# Bluetooth_Bee__Standalone_v1_0.net
KiCad netlist of a schematic drawn in EAGLE
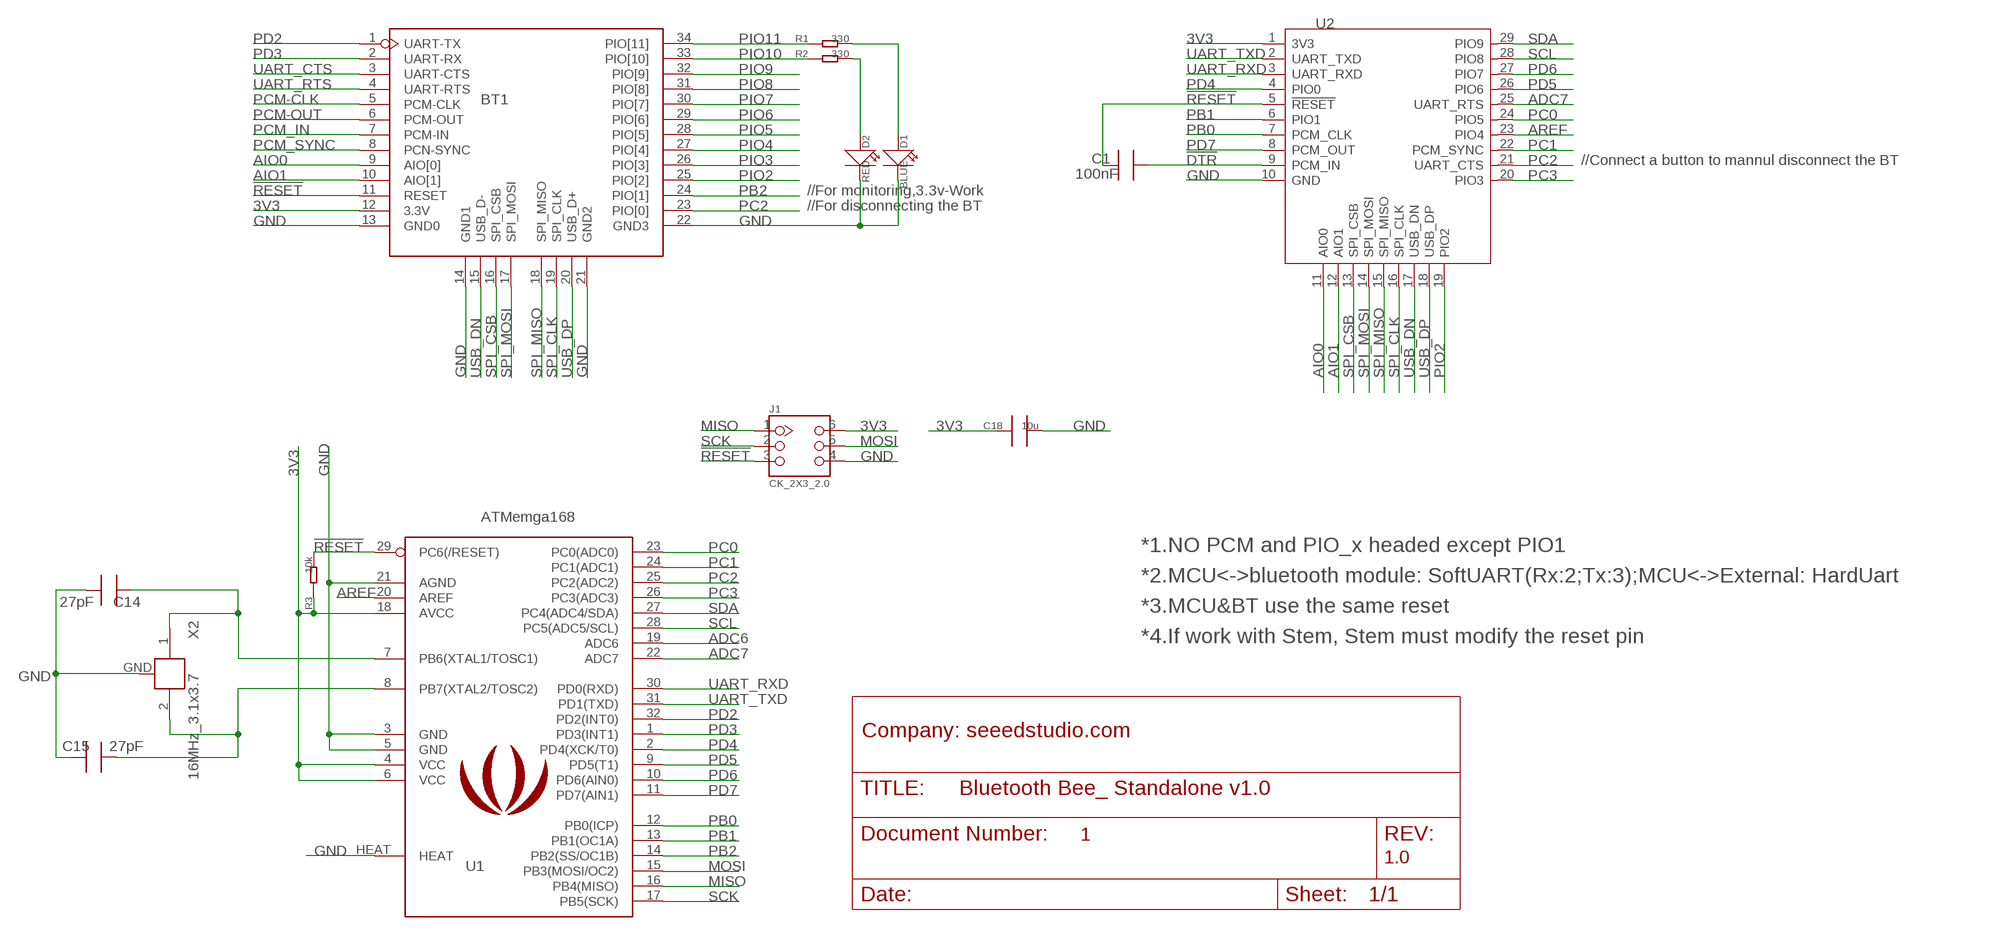
[diagram p0: schematic, sheet 1]

(export (version "E")
  (design (tool "Eeschema 10.0.6"))
  (components
    (comp (ref "BT1")
      (value "SERIAL_BLUETEETHSMT")
      (footprint "eagle-import:SERIAL_BLUETEETH")
      (libsource (lib "eagle-import") (part "SERIAL_BLUETEETHSMT"))
    )
    (comp (ref "C1")
      (value "100nF")
      (footprint "eagle-import:0603_S")
      (libsource (lib "eagle-import") (part "C0603_S"))
    )
    (comp (ref "C14")
      (value "27pF")
      (footprint "eagle-import:0603")
      (libsource (lib "eagle-import") (part "C0603"))
    )
    (comp (ref "C15")
      (value "27pF")
      (footprint "eagle-import:0603")
      (libsource (lib "eagle-import") (part "C0603"))
    )
    (comp (ref "C18")
      (value "10u")
      (footprint "eagle-import:0805")
      (libsource (lib "eagle-import") (part "C0805"))
    )
    (comp (ref "D1")
      (value "BLUE")
      (footprint "eagle-import:LED0603")
      (libsource (lib "eagle-import") (part "LED0603"))
    )
    (comp (ref "D2")
      (value "RED")
      (footprint "eagle-import:LED0603")
      (libsource (lib "eagle-import") (part "LED0603"))
    )
    (comp (ref "J1")
      (value "CK_2X3_2.0")
      (footprint "eagle-import:CK_2X3_2.0")
      (libsource (lib "eagle-import") (part "CK_2X3_2.0"))
    )
    (comp (ref "LOGO1")
      (value "LOGO_SILK")
      (footprint "eagle-import:LOGO_SILK")
      (libsource (lib "eagle-import") (part "LOGO_SILK"))
    )
    (comp (ref "R1")
      (value "330")
      (footprint "eagle-import:0603")
      (libsource (lib "eagle-import") (part "R0603"))
    )
    (comp (ref "R2")
      (value "330")
      (footprint "eagle-import:0603")
      (libsource (lib "eagle-import") (part "R0603"))
    )
    (comp (ref "R3")
      (value "10k")
      (footprint "eagle-import:0603_S@1")
      (libsource (lib "eagle-import") (part "R0603_S"))
    )
    (comp (ref "U1")
      (value "ATMemga168")
      (footprint "eagle-import:MLF32X")
      (libsource (lib "eagle-import") (part "MEGA8"))
    )
    (comp (ref "U2")
      (value "BLUTOOTHBEE-MS")
      (footprint "eagle-import:29P-DIP-2.0")
      (libsource (lib "eagle-import") (part "BLUTOOTHBEE-MS"))
    )
    (comp (ref "X2")
      (value "16MHz_3.1x3.7")
      (footprint "eagle-import:XTAL_NC")
      (libsource (lib "eagle-import") (part "XTAL_NCHOZ"))
    )
  )
  (nets
    (net (code "1") (name "/3V3") (class "Default")
      (node (ref "BT1") (pin "12") (pinfunction "3.3V_12") (pintype "bidirectional"))
      (node (ref "C18") (pin "1") (pinfunction "1_1") (pintype "bidirectional"))
      (node (ref "J1") (pin "6") (pinfunction "P$6_6") (pintype "bidirectional"))
      (node (ref "R3") (pin "1") (pinfunction "1_1") (pintype "bidirectional"))
      (node (ref "U1") (pin "18") (pinfunction "AVCC_18") (pintype "bidirectional"))
      (node (ref "U1") (pin "4") (pinfunction "VCC_4") (pintype "bidirectional"))
      (node (ref "U1") (pin "6") (pinfunction "VCC_6") (pintype "bidirectional"))
      (node (ref "U2") (pin "1") (pinfunction "3V3_1") (pintype "bidirectional"))
    )
    (net (code "2") (name "/ADC6") (class "Default")
      (node (ref "U1") (pin "19") (pinfunction "ADC6_19") (pintype "bidirectional"))
    )
    (net (code "3") (name "/ADC7") (class "Default")
      (node (ref "U1") (pin "22") (pinfunction "ADC7_22") (pintype "bidirectional"))
      (node (ref "U2") (pin "25") (pinfunction "UART_RTS_25") (pintype "bidirectional"))
    )
    (net (code "4") (name "/AIO0") (class "Default")
      (node (ref "BT1") (pin "9") (pinfunction "AIO[0]_9") (pintype "bidirectional"))
      (node (ref "U2") (pin "11") (pinfunction "AIO0_11") (pintype "bidirectional"))
    )
    (net (code "5") (name "/AIO1") (class "Default")
      (node (ref "BT1") (pin "10") (pinfunction "AIO[1]_10") (pintype "bidirectional"))
      (node (ref "U2") (pin "12") (pinfunction "AIO1_12") (pintype "bidirectional"))
    )
    (net (code "6") (name "/AREF") (class "Default")
      (node (ref "U1") (pin "20") (pinfunction "AREF_20") (pintype "bidirectional"))
      (node (ref "U2") (pin "23") (pinfunction "PIO4_23") (pintype "bidirectional"))
    )
    (net (code "7") (name "/GND") (class "Default")
      (node (ref "BT1") (pin "13") (pinfunction "GND0_13") (pintype "bidirectional"))
      (node (ref "BT1") (pin "14") (pinfunction "GND1_14") (pintype "bidirectional"))
      (node (ref "BT1") (pin "21") (pinfunction "GND2_21") (pintype "bidirectional"))
      (node (ref "BT1") (pin "22") (pinfunction "GND3_22") (pintype "bidirectional"))
      (node (ref "C14") (pin "2") (pinfunction "2_2") (pintype "bidirectional"))
      (node (ref "C15") (pin "1") (pinfunction "1_1") (pintype "bidirectional"))
      (node (ref "C18") (pin "2") (pinfunction "2_2") (pintype "bidirectional"))
      (node (ref "D1") (pin "2") (pinfunction "-_2") (pintype "bidirectional"))
      (node (ref "D2") (pin "2") (pinfunction "-_2") (pintype "bidirectional"))
      (node (ref "J1") (pin "4") (pinfunction "P$4_4") (pintype "bidirectional"))
      (node (ref "U1") (pin "21") (pinfunction "AGND_21") (pintype "bidirectional"))
      (node (ref "U1") (pin "3") (pinfunction "GND_3") (pintype "bidirectional"))
      (node (ref "U1") (pin "5") (pinfunction "GND_5") (pintype "bidirectional"))
      (node (ref "U1") (pin "HEAT") (pinfunction "HEAT_HEAT") (pintype "bidirectional"))
      (node (ref "U2") (pin "10") (pinfunction "GND_10") (pintype "bidirectional"))
      (node (ref "X2") (pin "GND") (pinfunction "GND_GND") (pintype "bidirectional"))
    )
    (net (code "8") (name "/MISO") (class "Default")
      (node (ref "J1") (pin "1") (pinfunction "P$1_1") (pintype "bidirectional"))
      (node (ref "U1") (pin "16") (pinfunction "PB4(MISO)_16") (pintype "bidirectional"))
    )
    (net (code "9") (name "/MOSI") (class "Default")
      (node (ref "J1") (pin "5") (pinfunction "P$5_5") (pintype "bidirectional"))
      (node (ref "U1") (pin "15") (pinfunction "PB3(MOSI/OC2)_15") (pintype "bidirectional"))
    )
    (net (code "10") (name "/PB0") (class "Default")
      (node (ref "U1") (pin "12") (pinfunction "PB0(ICP)_12") (pintype "bidirectional"))
      (node (ref "U2") (pin "7") (pinfunction "PCM_CLK_7") (pintype "bidirectional"))
    )
    (net (code "11") (name "/PB1") (class "Default")
      (node (ref "U1") (pin "13") (pinfunction "PB1(OC1A)_13") (pintype "bidirectional"))
      (node (ref "U2") (pin "6") (pinfunction "PIO1_6") (pintype "bidirectional"))
    )
    (net (code "12") (name "/PB2") (class "Default")
      (node (ref "BT1") (pin "24") (pinfunction "PIO[1]_24") (pintype "bidirectional"))
      (node (ref "U1") (pin "14") (pinfunction "PB2(SS/OC1B)_14") (pintype "bidirectional"))
    )
    (net (code "13") (name "/PC0") (class "Default")
      (node (ref "U1") (pin "23") (pinfunction "PC0(ADC0)_23") (pintype "bidirectional"))
      (node (ref "U2") (pin "24") (pinfunction "PIO5_24") (pintype "bidirectional"))
    )
    (net (code "14") (name "/PC1") (class "Default")
      (node (ref "U1") (pin "24") (pinfunction "PC1(ADC1)_24") (pintype "bidirectional"))
      (node (ref "U2") (pin "22") (pinfunction "PCM_SYNC_22") (pintype "bidirectional"))
    )
    (net (code "15") (name "/PC2") (class "Default")
      (node (ref "BT1") (pin "23") (pinfunction "PIO[0]_23") (pintype "bidirectional"))
      (node (ref "U1") (pin "25") (pinfunction "PC2(ADC2)_25") (pintype "bidirectional"))
      (node (ref "U2") (pin "21") (pinfunction "UART_CTS_21") (pintype "bidirectional"))
    )
    (net (code "16") (name "/PC3") (class "Default")
      (node (ref "U1") (pin "26") (pinfunction "PC3(ADC3)_26") (pintype "bidirectional"))
      (node (ref "U2") (pin "20") (pinfunction "PIO3_20") (pintype "bidirectional"))
    )
    (net (code "17") (name "/PCM-CLK") (class "Default")
      (node (ref "BT1") (pin "5") (pinfunction "PCM-CLK_5") (pintype "bidirectional"))
    )
    (net (code "18") (name "/PCM-OUT") (class "Default")
      (node (ref "BT1") (pin "6") (pinfunction "PCM-OUT_6") (pintype "bidirectional"))
    )
    (net (code "19") (name "/PCM_IN") (class "Default")
      (node (ref "BT1") (pin "7") (pinfunction "PCM-IN_7") (pintype "bidirectional"))
    )
    (net (code "20") (name "/PCM_SYNC") (class "Default")
      (node (ref "BT1") (pin "8") (pinfunction "PCN-SYNC_8") (pintype "bidirectional"))
    )
    (net (code "21") (name "/PD2") (class "Default")
      (node (ref "BT1") (pin "1") (pinfunction "UART-TX_1") (pintype "bidirectional"))
      (node (ref "U1") (pin "32") (pinfunction "PD2(INT0)_32") (pintype "bidirectional"))
    )
    (net (code "22") (name "/PD3") (class "Default")
      (node (ref "BT1") (pin "2") (pinfunction "UART-RX_2") (pintype "bidirectional"))
      (node (ref "U1") (pin "1") (pinfunction "PD3(INT1)_1") (pintype "bidirectional"))
    )
    (net (code "23") (name "/PD4") (class "Default")
      (node (ref "U1") (pin "2") (pinfunction "PD4(XCK/T0)_2") (pintype "bidirectional"))
      (node (ref "U2") (pin "4") (pinfunction "PIO0_4") (pintype "bidirectional"))
    )
    (net (code "24") (name "/PD5") (class "Default")
      (node (ref "U1") (pin "9") (pinfunction "PD5(T1)_9") (pintype "bidirectional"))
      (node (ref "U2") (pin "26") (pinfunction "PIO6_26") (pintype "bidirectional"))
    )
    (net (code "25") (name "/PD6") (class "Default")
      (node (ref "U1") (pin "10") (pinfunction "PD6(AIN0)_10") (pintype "bidirectional"))
      (node (ref "U2") (pin "27") (pinfunction "PIO7_27") (pintype "bidirectional"))
    )
    (net (code "26") (name "/PD7") (class "Default")
      (node (ref "U1") (pin "11") (pinfunction "PD7(AIN1)_11") (pintype "bidirectional"))
      (node (ref "U2") (pin "8") (pinfunction "PCM_OUT_8") (pintype "bidirectional"))
    )
    (net (code "27") (name "/PIO2") (class "Default")
      (node (ref "BT1") (pin "25") (pinfunction "PIO[2]_25") (pintype "bidirectional"))
      (node (ref "U2") (pin "19") (pinfunction "PIO2_19") (pintype "bidirectional"))
    )
    (net (code "28") (name "/PIO3") (class "Default")
      (node (ref "BT1") (pin "26") (pinfunction "PIO[3]_26") (pintype "bidirectional"))
    )
    (net (code "29") (name "/PIO4") (class "Default")
      (node (ref "BT1") (pin "27") (pinfunction "PIO[4]_27") (pintype "bidirectional"))
    )
    (net (code "30") (name "/PIO5") (class "Default")
      (node (ref "BT1") (pin "28") (pinfunction "PIO[5]_28") (pintype "bidirectional"))
    )
    (net (code "31") (name "/PIO6") (class "Default")
      (node (ref "BT1") (pin "29") (pinfunction "PIO[6]_29") (pintype "bidirectional"))
    )
    (net (code "32") (name "/PIO7") (class "Default")
      (node (ref "BT1") (pin "30") (pinfunction "PIO[7]_30") (pintype "bidirectional"))
    )
    (net (code "33") (name "/PIO8") (class "Default")
      (node (ref "BT1") (pin "31") (pinfunction "PIO[8]_31") (pintype "bidirectional"))
    )
    (net (code "34") (name "/PIO9") (class "Default")
      (node (ref "BT1") (pin "32") (pinfunction "PIO[9]_32") (pintype "bidirectional"))
    )
    (net (code "35") (name "/PIO10") (class "Default")
      (node (ref "BT1") (pin "33") (pinfunction "PIO[10]_33") (pintype "bidirectional"))
      (node (ref "R2") (pin "1") (pinfunction "1_1") (pintype "bidirectional"))
    )
    (net (code "36") (name "/PIO11") (class "Default")
      (node (ref "BT1") (pin "34") (pinfunction "PIO[11]_34") (pintype "bidirectional"))
      (node (ref "R1") (pin "1") (pinfunction "1_1") (pintype "bidirectional"))
    )
    (net (code "37") (name "/SCK") (class "Default")
      (node (ref "J1") (pin "2") (pinfunction "P$2_2") (pintype "bidirectional"))
      (node (ref "U1") (pin "17") (pinfunction "PB5(SCK)_17") (pintype "bidirectional"))
    )
    (net (code "38") (name "/SCL") (class "Default")
      (node (ref "U1") (pin "28") (pinfunction "PC5(ADC5/SCL)_28") (pintype "bidirectional"))
      (node (ref "U2") (pin "28") (pinfunction "PIO8_28") (pintype "bidirectional"))
    )
    (net (code "39") (name "/SDA") (class "Default")
      (node (ref "U1") (pin "27") (pinfunction "PC4(ADC4/SDA)_27") (pintype "bidirectional"))
      (node (ref "U2") (pin "29") (pinfunction "PIO9_29") (pintype "bidirectional"))
    )
    (net (code "40") (name "/SPI_CLK") (class "Default")
      (node (ref "BT1") (pin "19") (pinfunction "SPI_CLK_19") (pintype "bidirectional"))
      (node (ref "U2") (pin "16") (pinfunction "SPI_CLK_16") (pintype "bidirectional"))
    )
    (net (code "41") (name "/SPI_CSB") (class "Default")
      (node (ref "BT1") (pin "16") (pinfunction "SPI_CSB_16") (pintype "bidirectional"))
      (node (ref "U2") (pin "13") (pinfunction "SPI_CSB_13") (pintype "bidirectional"))
    )
    (net (code "42") (name "/SPI_MISO") (class "Default")
      (node (ref "BT1") (pin "18") (pinfunction "SPI_MISO_18") (pintype "bidirectional"))
      (node (ref "U2") (pin "15") (pinfunction "SPI_MISO_15") (pintype "bidirectional"))
    )
    (net (code "43") (name "/SPI_MOSI") (class "Default")
      (node (ref "BT1") (pin "17") (pinfunction "SPI_MOSI_17") (pintype "bidirectional"))
      (node (ref "U2") (pin "14") (pinfunction "SPI_MOSI_14") (pintype "bidirectional"))
    )
    (net (code "44") (name "/UART_CTS") (class "Default")
      (node (ref "BT1") (pin "3") (pinfunction "UART-CTS_3") (pintype "bidirectional"))
    )
    (net (code "45") (name "/UART_RTS") (class "Default")
      (node (ref "BT1") (pin "4") (pinfunction "UART-RTS_4") (pintype "bidirectional"))
    )
    (net (code "46") (name "/UART_RXD") (class "Default")
      (node (ref "U1") (pin "30") (pinfunction "PD0(RXD)_30") (pintype "bidirectional"))
      (node (ref "U2") (pin "3") (pinfunction "UART_RXD_3") (pintype "bidirectional"))
    )
    (net (code "47") (name "/UART_TXD") (class "Default")
      (node (ref "U1") (pin "31") (pinfunction "PD1(TXD)_31") (pintype "bidirectional"))
      (node (ref "U2") (pin "2") (pinfunction "UART_TXD_2") (pintype "bidirectional"))
    )
    (net (code "48") (name "/USB_DN") (class "Default")
      (node (ref "BT1") (pin "15") (pinfunction "USB_D-_15") (pintype "bidirectional"))
      (node (ref "U2") (pin "17") (pinfunction "USB_DN_17") (pintype "bidirectional"))
    )
    (net (code "49") (name "/USB_DP") (class "Default")
      (node (ref "BT1") (pin "20") (pinfunction "USB_D+_20") (pintype "bidirectional"))
      (node (ref "U2") (pin "18") (pinfunction "USB_DP_18") (pintype "bidirectional"))
    )
    (net (code "50") (name "/~{DTR}") (class "Default")
      (node (ref "C1") (pin "1") (pinfunction "1_1") (pintype "bidirectional"))
      (node (ref "U2") (pin "9") (pinfunction "PCM_IN_9") (pintype "bidirectional"))
    )
    (net (code "51") (name "/~{RESET}") (class "Default")
      (node (ref "BT1") (pin "11") (pinfunction "RESET_11") (pintype "bidirectional"))
      (node (ref "C1") (pin "2") (pinfunction "2_2") (pintype "bidirectional"))
      (node (ref "J1") (pin "3") (pinfunction "P$3_3") (pintype "bidirectional"))
      (node (ref "R3") (pin "2") (pinfunction "2_2") (pintype "bidirectional"))
      (node (ref "U1") (pin "29") (pinfunction "PC6(/RESET)_29") (pintype "bidirectional"))
      (node (ref "U2") (pin "5") (pinfunction "~{RESET}_5") (pintype "bidirectional"))
    )
    (net (code "52") (name "Net-(D1-+)") (class "Default")
      (node (ref "D1") (pin "1") (pinfunction "+_1") (pintype "bidirectional"))
      (node (ref "R1") (pin "2") (pinfunction "2_2") (pintype "bidirectional"))
    )
    (net (code "53") (name "Net-(D2-+)") (class "Default")
      (node (ref "D2") (pin "1") (pinfunction "+_1") (pintype "bidirectional"))
      (node (ref "R2") (pin "2") (pinfunction "2_2") (pintype "bidirectional"))
    )
    (net (code "54") (name "Net-(U1-PB6(XTAL1{slash}TOSC1))") (class "Default")
      (node (ref "C14") (pin "1") (pinfunction "1_1") (pintype "bidirectional"))
      (node (ref "U1") (pin "7") (pinfunction "PB6(XTAL1/TOSC1)_7") (pintype "bidirectional"))
      (node (ref "X2") (pin "1") (pinfunction "1_1") (pintype "bidirectional"))
    )
    (net (code "55") (name "Net-(U1-PB7(XTAL2{slash}TOSC2))") (class "Default")
      (node (ref "C15") (pin "2") (pinfunction "2_2") (pintype "bidirectional"))
      (node (ref "U1") (pin "8") (pinfunction "PB7(XTAL2/TOSC2)_8") (pintype "bidirectional"))
      (node (ref "X2") (pin "2") (pinfunction "2_2") (pintype "bidirectional"))
    )
  )
)
